# power_supply.net
KiCad netlist of a schematic drawn in Altium Designer
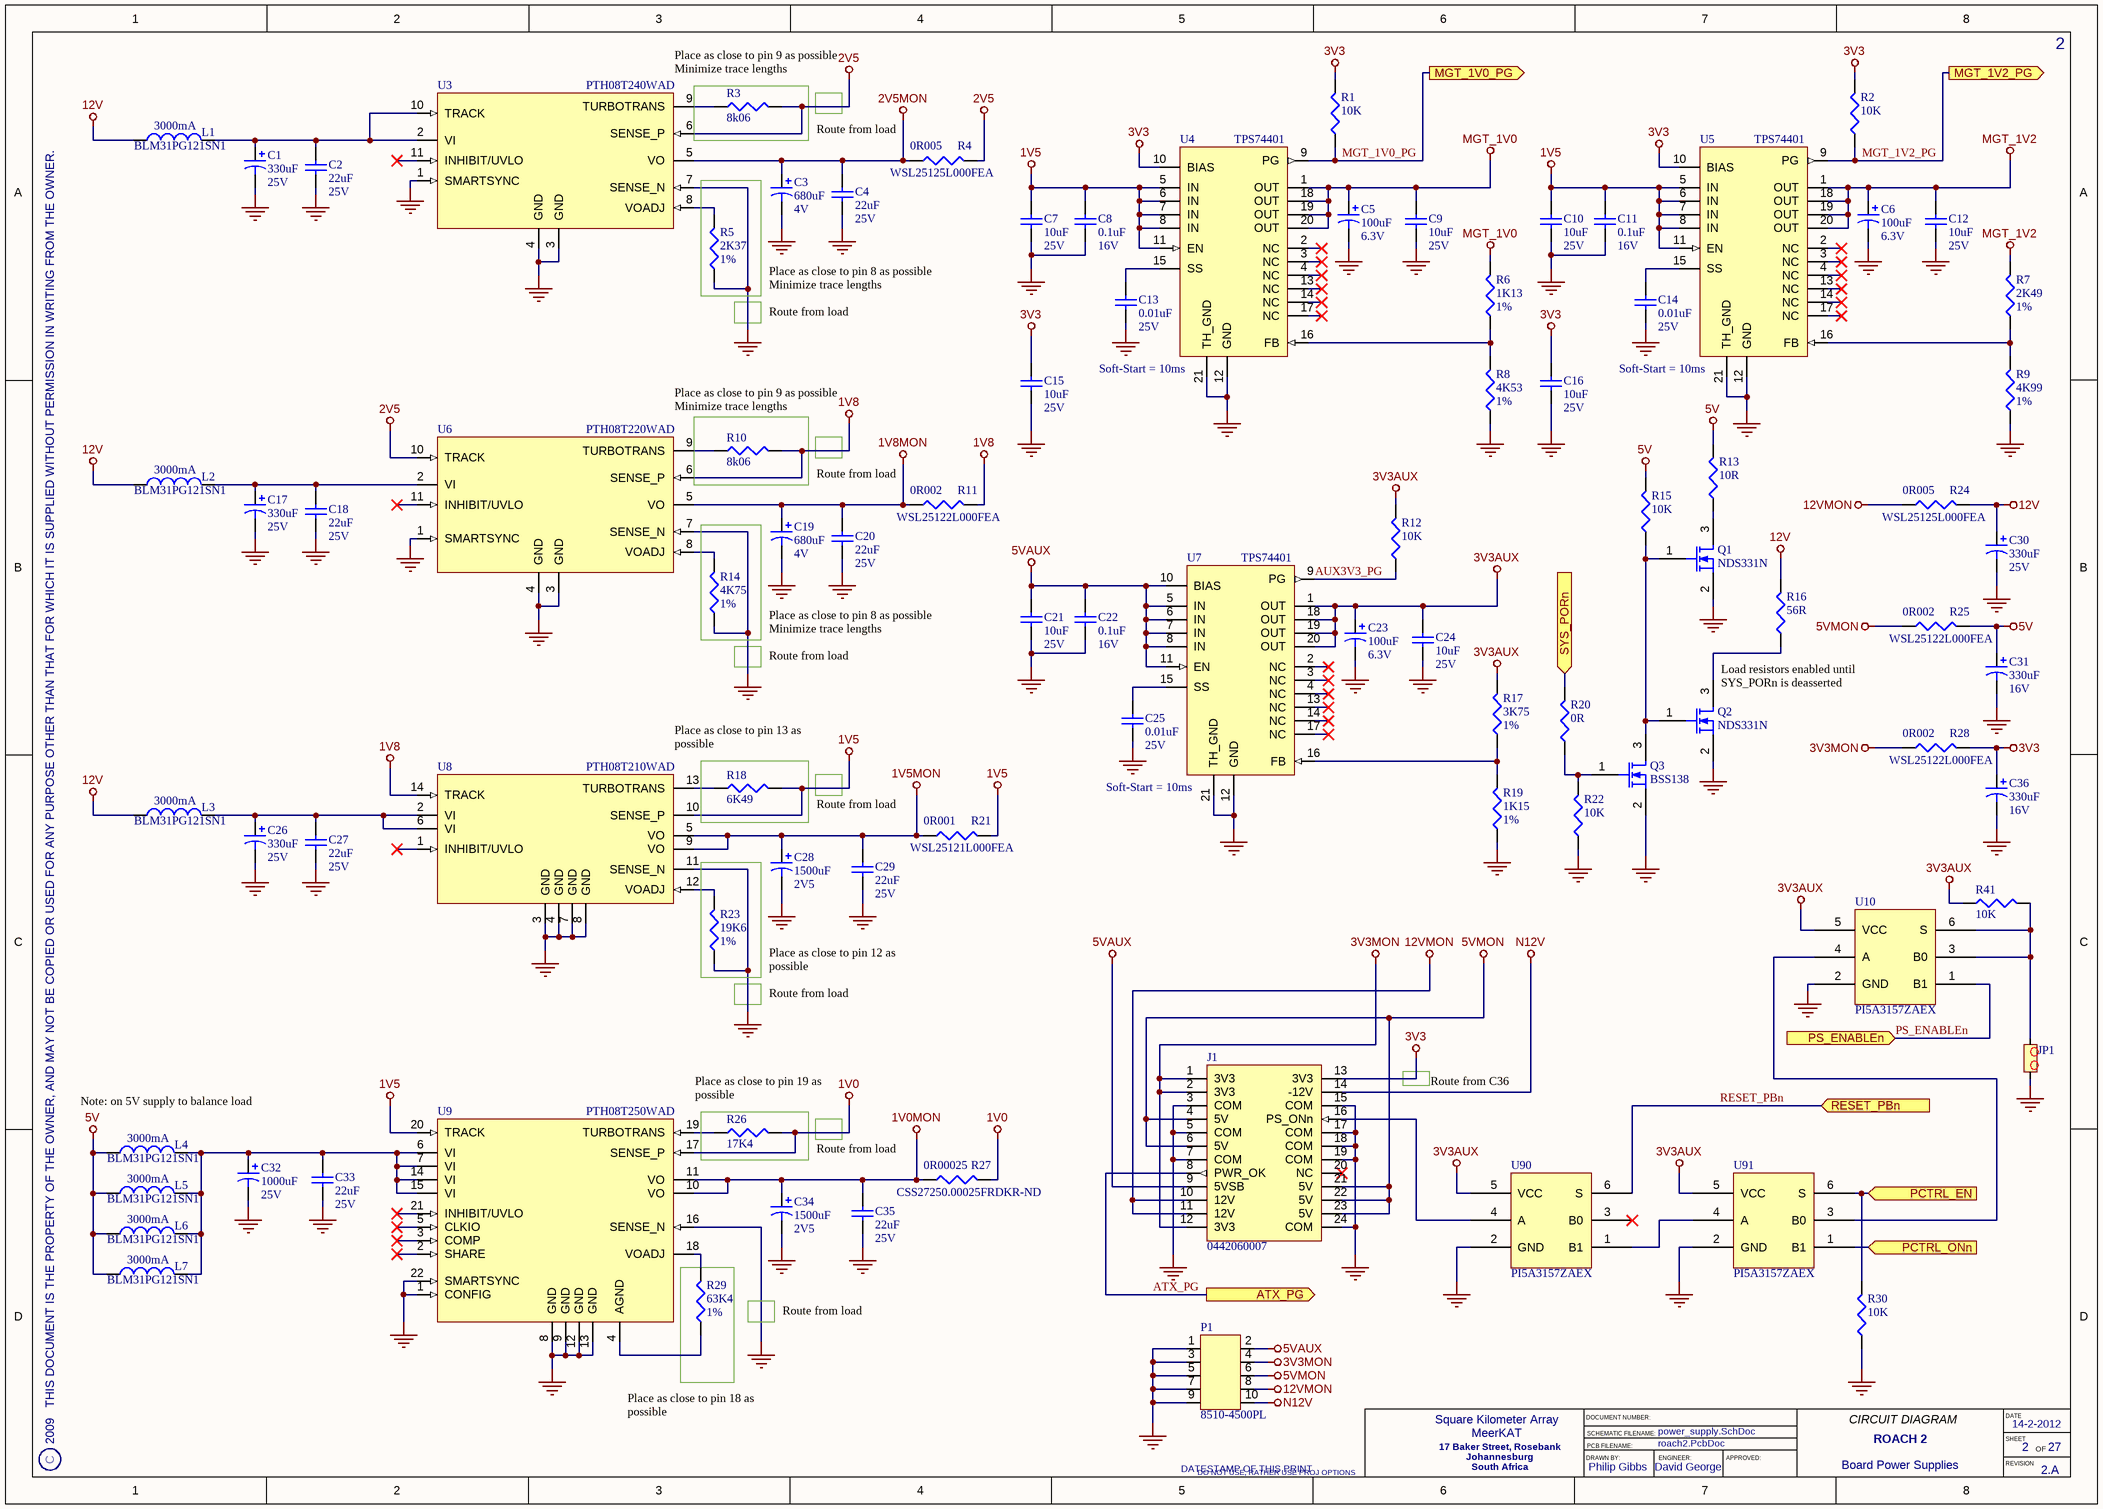
[diagram p0: power_supply.SchDoc]

(export (version "E")
  (design (tool "Eeschema 10.0.6"))
  (components
    (comp (ref "C1")
      (value "330uF")
      (footprint "EEE1CA331UP")
      (description "330uF, Surface Mount, Radial, Aluminium Electrolytic Capacitor")
      (fields
        (field (name "RATING") "25V")
        (field (name "MANUFACTURER") "PANASONIC-ECG")
        (field (name "PARTNUM") "EEE1EA331UP")
      )
      (libsource (lib "altium_db") (part "CapPol"))
    )
    (comp (ref "C2")
      (value "22uF")
      (footprint "CAPC3225X270L")
      (description "22uF, Ceramic Capacitor")
      (fields
        (field (name "RATING") "25V")
        (field (name "MANUFACTURER") "MURATA")
        (field (name "PARTNUM") "GRM32ER61E226ME15L")
      )
      (libsource (lib "altium_db") (part "CapStd"))
    )
    (comp (ref "C3")
      (value "680uF")
      (footprint "CAPMP7343X430L")
      (description "680uF, Conductive Polymer Chip Capacitor")
      (fields
        (field (name "RATING") "4V")
        (field (name "MANUFACTURER") "KEMET")
        (field (name "PARTNUM") "T520Y687M004ATE015")
      )
      (libsource (lib "altium_db") (part "CapPol"))
    )
    (comp (ref "C4")
      (value "22uF")
      (footprint "CAPC3225X270L")
      (description "22uF, Ceramic Capacitor")
      (fields
        (field (name "RATING") "25V")
        (field (name "MANUFACTURER") "MURATA")
        (field (name "PARTNUM") "GRM32ER61E226ME15L")
      )
      (libsource (lib "altium_db") (part "CapStd"))
    )
    (comp (ref "C5")
      (value "100uF")
      (footprint "CAPMP3528X210L")
      (description "100uF, Low ESR, Tantalum Capacitor")
      (fields
        (field (name "RATING") "6.3V")
        (field (name "MANUFACTURER") "AVX")
        (field (name "PARTNUM") "TPSB107M006R0200")
      )
      (libsource (lib "altium_db") (part "CapPol"))
    )
    (comp (ref "C6")
      (value "100uF")
      (footprint "CAPMP3528X210L")
      (description "100uF, Low ESR, Tantalum Capacitor")
      (fields
        (field (name "RATING") "6.3V")
        (field (name "MANUFACTURER") "AVX")
        (field (name "PARTNUM") "TPSB107M006R0200")
      )
      (libsource (lib "altium_db") (part "CapPol"))
    )
    (comp (ref "C7")
      (value "10uF")
      (footprint "CAPC3225X200L")
      (description "10uF, Ceramic Capacitor")
      (fields
        (field (name "RATING") "25V")
        (field (name "MANUFACTURER") "MURATA")
        (field (name "PARTNUM") "GRM32DR61E106KA12L")
      )
      (libsource (lib "altium_db") (part "CapStd"))
    )
    (comp (ref "C8")
      (value "0.1uF")
      (footprint "CAPC1005X60L")
      (description "0.1uF, Ceramic Capacitor")
      (fields
        (field (name "RATING") "16V")
        (field (name "MANUFACTURER") "VENKEL")
        (field (name "PARTNUM") "C0402X7R160-104KN")
      )
      (libsource (lib "altium_db") (part "CapStd"))
    )
    (comp (ref "C9")
      (value "10uF")
      (footprint "CAPC3225X200L")
      (description "10uF, Ceramic Capacitor")
      (fields
        (field (name "RATING") "25V")
        (field (name "MANUFACTURER") "MURATA")
        (field (name "PARTNUM") "GRM32DR61E106KA12L")
      )
      (libsource (lib "altium_db") (part "CapStd"))
    )
    (comp (ref "C10")
      (value "10uF")
      (footprint "CAPC3225X200L")
      (description "10uF, Ceramic Capacitor")
      (fields
        (field (name "RATING") "25V")
        (field (name "MANUFACTURER") "MURATA")
        (field (name "PARTNUM") "GRM32DR61E106KA12L")
      )
      (libsource (lib "altium_db") (part "CapStd"))
    )
    (comp (ref "C11")
      (value "0.1uF")
      (footprint "CAPC1005X60L")
      (description "0.1uF, Ceramic Capacitor")
      (fields
        (field (name "RATING") "16V")
        (field (name "MANUFACTURER") "VENKEL")
        (field (name "PARTNUM") "C0402X7R160-104KN")
      )
      (libsource (lib "altium_db") (part "CapStd"))
    )
    (comp (ref "C12")
      (value "10uF")
      (footprint "CAPC3225X200L")
      (description "10uF, Ceramic Capacitor")
      (fields
        (field (name "RATING") "25V")
        (field (name "MANUFACTURER") "MURATA")
        (field (name "PARTNUM") "GRM32DR61E106KA12L")
      )
      (libsource (lib "altium_db") (part "CapStd"))
    )
    (comp (ref "C13")
      (value "0.01uF")
      (footprint "CAPC1005X55L")
      (description "0.01uF, Ceramic Capacitor")
      (fields
        (field (name "RATING") "25V")
        (field (name "MANUFACTURER") "MURATA")
        (field (name "PARTNUM") "GRM155R71E103KA01D")
      )
      (libsource (lib "altium_db") (part "CapStd"))
    )
    (comp (ref "C14")
      (value "0.01uF")
      (footprint "CAPC1005X55L")
      (description "0.01uF, Ceramic Capacitor")
      (fields
        (field (name "RATING") "25V")
        (field (name "MANUFACTURER") "MURATA")
        (field (name "PARTNUM") "GRM155R71E103KA01D")
      )
      (libsource (lib "altium_db") (part "CapStd"))
    )
    (comp (ref "C15")
      (value "10uF")
      (footprint "CAPC3225X200L")
      (description "10uF, Ceramic Capacitor")
      (fields
        (field (name "RATING") "25V")
        (field (name "MANUFACTURER") "MURATA")
        (field (name "PARTNUM") "GRM32DR61E106KA12L")
      )
      (libsource (lib "altium_db") (part "CapStd"))
    )
    (comp (ref "C16")
      (value "10uF")
      (footprint "CAPC3225X200L")
      (description "10uF, Ceramic Capacitor")
      (fields
        (field (name "RATING") "25V")
        (field (name "MANUFACTURER") "MURATA")
        (field (name "PARTNUM") "GRM32DR61E106KA12L")
      )
      (libsource (lib "altium_db") (part "CapStd"))
    )
    (comp (ref "C17")
      (value "330uF")
      (footprint "EEE1CA331UP")
      (description "330uF, Surface Mount, Radial, Aluminium Electrolytic Capacitor")
      (fields
        (field (name "RATING") "25V")
        (field (name "MANUFACTURER") "PANASONIC-ECG")
        (field (name "PARTNUM") "EEE1EA331UP")
      )
      (libsource (lib "altium_db") (part "CapPol"))
    )
    (comp (ref "C18")
      (value "22uF")
      (footprint "CAPC3225X270L")
      (description "22uF, Ceramic Capacitor")
      (fields
        (field (name "RATING") "25V")
        (field (name "MANUFACTURER") "MURATA")
        (field (name "PARTNUM") "GRM32ER61E226ME15L")
      )
      (libsource (lib "altium_db") (part "CapStd"))
    )
    (comp (ref "C19")
      (value "680uF")
      (footprint "CAPMP7343X430L")
      (description "680uF, Conductive Polymer Chip Capacitor")
      (fields
        (field (name "RATING") "4V")
        (field (name "MANUFACTURER") "KEMET")
        (field (name "PARTNUM") "T520Y687M004ATE015")
      )
      (libsource (lib "altium_db") (part "CapPol"))
    )
    (comp (ref "C20")
      (value "22uF")
      (footprint "CAPC3225X270L")
      (description "22uF, Ceramic Capacitor")
      (fields
        (field (name "RATING") "25V")
        (field (name "MANUFACTURER") "MURATA")
        (field (name "PARTNUM") "GRM32ER61E226ME15L")
      )
      (libsource (lib "altium_db") (part "CapStd"))
    )
    (comp (ref "C21")
      (value "10uF")
      (footprint "CAPC3225X200L")
      (description "10uF, Ceramic Capacitor")
      (fields
        (field (name "RATING") "25V")
        (field (name "MANUFACTURER") "MURATA")
        (field (name "PARTNUM") "GRM32DR61E106KA12L")
      )
      (libsource (lib "altium_db") (part "CapStd"))
    )
    (comp (ref "C22")
      (value "0.1uF")
      (footprint "CAPC1005X60L")
      (description "0.1uF, Ceramic Capacitor")
      (fields
        (field (name "RATING") "16V")
        (field (name "MANUFACTURER") "VENKEL")
        (field (name "PARTNUM") "C0402X7R160-104KN")
      )
      (libsource (lib "altium_db") (part "CapStd"))
    )
    (comp (ref "C23")
      (value "100uF")
      (footprint "CAPMP3528X210L")
      (description "100uF, Low ESR, Tantalum Capacitor")
      (fields
        (field (name "RATING") "6.3V")
        (field (name "MANUFACTURER") "AVX")
        (field (name "PARTNUM") "TPSB107M006R0200")
      )
      (libsource (lib "altium_db") (part "CapPol"))
    )
    (comp (ref "C24")
      (value "10uF")
      (footprint "CAPC3225X200L")
      (description "10uF, Ceramic Capacitor")
      (fields
        (field (name "RATING") "25V")
        (field (name "MANUFACTURER") "MURATA")
        (field (name "PARTNUM") "GRM32DR61E106KA12L")
      )
      (libsource (lib "altium_db") (part "CapStd"))
    )
    (comp (ref "C25")
      (value "0.01uF")
      (footprint "CAPC1005X55L")
      (description "0.01uF, Ceramic Capacitor")
      (fields
        (field (name "RATING") "25V")
        (field (name "MANUFACTURER") "MURATA")
        (field (name "PARTNUM") "GRM155R71E103KA01D")
      )
      (libsource (lib "altium_db") (part "CapStd"))
    )
    (comp (ref "C26")
      (value "330uF")
      (footprint "EEE1CA331UP")
      (description "330uF, Surface Mount, Radial, Aluminium Electrolytic Capacitor")
      (fields
        (field (name "RATING") "25V")
        (field (name "MANUFACTURER") "PANASONIC-ECG")
        (field (name "PARTNUM") "EEE1EA331UP")
      )
      (libsource (lib "altium_db") (part "CapPol"))
    )
    (comp (ref "C27")
      (value "22uF")
      (footprint "CAPC3225X270L")
      (description "22uF, Ceramic Capacitor")
      (fields
        (field (name "RATING") "25V")
        (field (name "MANUFACTURER") "MURATA")
        (field (name "PARTNUM") "GRM32ER61E226ME15L")
      )
      (libsource (lib "altium_db") (part "CapStd"))
    )
    (comp (ref "C28")
      (value "1500uF")
      (footprint "CAPMP7343X430L")
      (description "1500uF, Conductive Polymer Chip Capacitor")
      (fields
        (field (name "RATING") "2V5")
        (field (name "MANUFACTURER") "KEMET")
        (field (name "PARTNUM") "T530X158M2R5ATE005")
      )
      (libsource (lib "altium_db") (part "CapPol"))
    )
    (comp (ref "C29")
      (value "22uF")
      (footprint "CAPC3225X270L")
      (description "22uF, Ceramic Capacitor")
      (fields
        (field (name "RATING") "25V")
        (field (name "MANUFACTURER") "MURATA")
        (field (name "PARTNUM") "GRM32ER61E226ME15L")
      )
      (libsource (lib "altium_db") (part "CapStd"))
    )
    (comp (ref "C30")
      (value "330uF")
      (footprint "EEE1CA331UP")
      (description "330uF, Surface Mount, Radial, Aluminium Electrolytic Capacitor")
      (fields
        (field (name "RATING") "25V")
        (field (name "MANUFACTURER") "PANASONIC-ECG")
        (field (name "PARTNUM") "EEE1EA331UP")
      )
      (libsource (lib "altium_db") (part "CapPol"))
    )
    (comp (ref "C31")
      (value "330uF")
      (footprint "CAPMP7263X380L")
      (description "330uF, Solid Tantalum Chip Capacitor")
      (fields
        (field (name "RATING") "16V")
        (field (name "MANUFACTURER") "VISHAY")
        (field (name "PARTNUM") "594D337X0016R2T")
      )
      (libsource (lib "altium_db") (part "CapPol"))
    )
    (comp (ref "C32")
      (value "1000uF")
      (footprint "CAPPRD750W80D1600H1500P")
      (description "1000uF, Aluminium Electrolytic Capacitor")
      (fields
        (field (name "RATING") "25V")
        (field (name "MANUFACTURER") "PANASONIC-ECG")
        (field (name "PARTNUM") "EEUFC1E102S")
      )
      (libsource (lib "altium_db") (part "CapPol"))
    )
    (comp (ref "C33")
      (value "22uF")
      (footprint "CAPC3225X270L")
      (description "22uF, Ceramic Capacitor")
      (fields
        (field (name "RATING") "25V")
        (field (name "MANUFACTURER") "MURATA")
        (field (name "PARTNUM") "GRM32ER61E226ME15L")
      )
      (libsource (lib "altium_db") (part "CapStd"))
    )
    (comp (ref "C34")
      (value "1500uF")
      (footprint "CAPMP7343X430L")
      (description "1500uF, Conductive Polymer Chip Capacitor")
      (fields
        (field (name "RATING") "2V5")
        (field (name "MANUFACTURER") "KEMET")
        (field (name "PARTNUM") "T530X158M2R5ATE005")
      )
      (libsource (lib "altium_db") (part "CapPol"))
    )
    (comp (ref "C35")
      (value "22uF")
      (footprint "CAPC3225X270L")
      (description "22uF, Ceramic Capacitor")
      (fields
        (field (name "RATING") "25V")
        (field (name "MANUFACTURER") "MURATA")
        (field (name "PARTNUM") "GRM32ER61E226ME15L")
      )
      (libsource (lib "altium_db") (part "CapStd"))
    )
    (comp (ref "C36")
      (value "330uF")
      (footprint "CAPMP7263X380L")
      (description "330uF, Solid Tantalum Chip Capacitor")
      (fields
        (field (name "RATING") "16V")
        (field (name "MANUFACTURER") "VISHAY")
        (field (name "PARTNUM") "594D337X0016R2T")
      )
      (libsource (lib "altium_db") (part "CapPol"))
    )
    (comp (ref "J1")
      (value "0442060007")
      (footprint "MOLEX_0442060007")
      (description "24-Pin ATX Connector")
      (fields (field (name "PARTNUM") "0442060007") (field (name "MANUFACTURER") "Molex"))
      (libsource (lib "altium_db") (part "0442060007"))
    )
    (comp (ref "JP1")
      (value "0022032021")
      (footprint "MOLEX_0022032021")
      (description "1x2, 2.56mm, Header/Jumper")
      (fields (field (name "MANUFACTURER") "Molex"))
      (libsource (lib "altium_db") (part "con_hdr_1x2"))
    )
    (comp (ref "L1")
      (value "120R")
      (footprint "INDC3216X130L")
      (description "120 Ohm, Chip Ferrite Brad")
      (fields
        (field (name "RATING") "3000mA")
        (field (name "MANUFACTURER") "Murata")
        (field (name "PARTNUM") "BLM31PG121SN1")
        (field (name "TOLERANCE") "25%")
      )
      (libsource (lib "altium_db") (part "IndStd"))
    )
    (comp (ref "L2")
      (value "120R")
      (footprint "INDC3216X130L")
      (description "120 Ohm, Chip Ferrite Brad")
      (fields
        (field (name "RATING") "3000mA")
        (field (name "MANUFACTURER") "Murata")
        (field (name "PARTNUM") "BLM31PG121SN1")
        (field (name "TOLERANCE") "25%")
      )
      (libsource (lib "altium_db") (part "IndStd"))
    )
    (comp (ref "L3")
      (value "120R")
      (footprint "INDC3216X130L")
      (description "120 Ohm, Chip Ferrite Brad")
      (fields
        (field (name "RATING") "3000mA")
        (field (name "MANUFACTURER") "Murata")
        (field (name "PARTNUM") "BLM31PG121SN1")
        (field (name "TOLERANCE") "25%")
      )
      (libsource (lib "altium_db") (part "IndStd"))
    )
    (comp (ref "L4")
      (value "120R")
      (footprint "INDC3216X130L")
      (description "120 Ohm, Chip Ferrite Brad")
      (fields
        (field (name "RATING") "3000mA")
        (field (name "MANUFACTURER") "Murata")
        (field (name "PARTNUM") "BLM31PG121SN1")
        (field (name "TOLERANCE") "25%")
      )
      (libsource (lib "altium_db") (part "IndStd"))
    )
    (comp (ref "L5")
      (value "120R")
      (footprint "INDC3216X130L")
      (description "120 Ohm, Chip Ferrite Brad")
      (fields
        (field (name "RATING") "3000mA")
        (field (name "MANUFACTURER") "Murata")
        (field (name "PARTNUM") "BLM31PG121SN1")
        (field (name "TOLERANCE") "25%")
      )
      (libsource (lib "altium_db") (part "IndStd"))
    )
    (comp (ref "L6")
      (value "120R")
      (footprint "INDC3216X130L")
      (description "120 Ohm, Chip Ferrite Brad")
      (fields
        (field (name "RATING") "3000mA")
        (field (name "MANUFACTURER") "Murata")
        (field (name "PARTNUM") "BLM31PG121SN1")
        (field (name "TOLERANCE") "25%")
      )
      (libsource (lib "altium_db") (part "IndStd"))
    )
    (comp (ref "L7")
      (value "120R")
      (footprint "INDC3216X130L")
      (description "120 Ohm, Chip Ferrite Brad")
      (fields
        (field (name "RATING") "3000mA")
        (field (name "MANUFACTURER") "Murata")
        (field (name "PARTNUM") "BLM31PG121SN1")
        (field (name "TOLERANCE") "25%")
      )
      (libsource (lib "altium_db") (part "IndStd"))
    )
    (comp (ref "P1")
      (value "8510-4500PL")
      (footprint "3M_8510-4500PL")
      (description "2x5, 2.54 mm Pitch, Through-hole, 1 Amp, Female Header")
      (fields (field (name "PARTNUM") "8510-4500PL") (field (name "MANUFACTURER") "3M"))
      (libsource (lib "altium_db") (part "con_hdr_2x5"))
    )
    (comp (ref "Q1")
      (value "NDS331N")
      (footprint "SOT95P245X110-3N")
      (description "N-Channel Logic Level Enhancement Mode Field Effect Transistor")
      (fields (field (name "MANUFACTURER") "Fairchild Semiconductor"))
      (libsource (lib "altium_db") (part "NDS331N"))
    )
    (comp (ref "Q2")
      (value "NDS331N")
      (footprint "SOT95P245X110-3N")
      (description "N-Channel Logic Level Enhancement Mode Field Effect Transistor")
      (fields (field (name "MANUFACTURER") "Fairchild Semiconductor"))
      (libsource (lib "altium_db") (part "NDS331N"))
    )
    (comp (ref "Q3")
      (value "BSS138")
      (footprint "SOT95P245X110-3N")
      (description "N-Channel Logic Level Enhancement Mode Field Effect Transistor")
      (fields (field (name "MANUFACTURER") "Fairchild Semiconductor"))
      (libsource (lib "altium_db") (part "BSS138"))
    )
    (comp (ref "R1")
      (value "10K")
      (footprint "RESC1005X40L")
      (description "10K, 1.1mm x 0.5mm, Thick Film Resistor")
      (fields (field (name "MANUFACTURER") "ROYALOHM") (field (name "PARTNUM") "0402WGJ0103T1E"))
      (libsource (lib "altium_db") (part "ResStd"))
    )
    (comp (ref "R2")
      (value "10K")
      (footprint "RESC1005X40L")
      (description "10K, 1.1mm x 0.5mm, Thick Film Resistor")
      (fields (field (name "MANUFACTURER") "ROYALOHM") (field (name "PARTNUM") "0402WGJ0103T1E"))
      (libsource (lib "altium_db") (part "ResStd"))
    )
    (comp (ref "R3")
      (value "8k06")
      (footprint "RESC1005X40L")
      (description "8K06, 1.1mm x 0.5mm, Thick Film Resistor")
      (fields (field (name "Comment") "ResStd"))
      (libsource (lib "altium_db") (part "ResStd"))
    )
    (comp (ref "R4")
      (value "0R005")
      (footprint "RESC6332X90M")
      (description "5 milliohm, Power Metal Strip, Sense Resistor")
      (fields
        (field (name "MANUFACTURER") "VISHAY")
        (field (name "PARTNUM") "WSL25125L000FEA")
        (field (name "TOLERANCE") "1%")
      )
      (libsource (lib "altium_db") (part "ResStd"))
    )
    (comp (ref "R5")
      (value "2K37")
      (footprint "RESC1005X40L")
      (description "2K37, 1.1mm x 0.5mm, Thick Film Resistor")
      (fields
        (field (name "MANUFACTURER") "ROYALOHM")
        (field (name "PARTNUM") "0402WGF2371T1E")
        (field (name "TOLERANCE") "1%")
      )
      (libsource (lib "altium_db") (part "ResStd"))
    )
    (comp (ref "R6")
      (value "1K13")
      (footprint "RESC1005X40L")
      (description "1K13, 1.1mm x 0.5mm, Thick Film Resistor")
      (fields
        (field (name "MANUFACTURER") "ROYALOHM")
        (field (name "PARTNUM") "0402WGF1131T1E")
        (field (name "TOLERANCE") "1%")
      )
      (libsource (lib "altium_db") (part "ResStd"))
    )
    (comp (ref "R7")
      (value "2K49")
      (footprint "RESC1005X40L")
      (description "2K49, 1.1mm x 0.5mm, Thick Film Resistor")
      (fields
        (field (name "MANUFACTURER") "ROYALOHM")
        (field (name "PARTNUM") "0402WGF2K49T1E")
        (field (name "TOLERANCE") "1%")
      )
      (libsource (lib "altium_db") (part "ResStd"))
    )
    (comp (ref "R8")
      (value "4K53")
      (footprint "RESC1005X40L")
      (description "4K53, 1.1mm x 0.5mm, Thick Film Resistor")
      (fields
        (field (name "MANUFACTURER") "ROYALOHM")
        (field (name "PARTNUM") "0402WGF4531T1E")
        (field (name "TOLERANCE") "1%")
      )
      (libsource (lib "altium_db") (part "ResStd"))
    )
    (comp (ref "R9")
      (value "4K99")
      (footprint "RESC1005X40L")
      (description "4K99, 1.1mm x 0.5mm, Thick Film Resistor")
      (fields
        (field (name "MANUFACTURER") "ROYALOHM")
        (field (name "PARTNUM") "0402WGF4991T1E")
        (field (name "TOLERANCE") "1%")
      )
      (libsource (lib "altium_db") (part "ResStd"))
    )
    (comp (ref "R10")
      (value "8k06")
      (footprint "RESC1005X40L")
      (description "8K06, 1.1mm x 0.5mm, Thick Film Resistor")
      (fields (field (name "Comment") "ResStd"))
      (libsource (lib "altium_db") (part "ResStd"))
    )
    (comp (ref "R11")
      (value "0R002")
      (footprint "RESC6332X90M")
      (description "2 milliohm, Power Metal Strip, Sense Resistor")
      (fields
        (field (name "MANUFACTURER") "VISHAY")
        (field (name "PARTNUM") "WSL25122L000FEA")
        (field (name "TOLERANCE") "1%")
      )
      (libsource (lib "altium_db") (part "ResStd"))
    )
    (comp (ref "R12")
      (value "10K")
      (footprint "RESC1005X40L")
      (description "10K, 1.1mm x 0.5mm, Thick Film Resistor")
      (fields (field (name "MANUFACTURER") "ROYALOHM") (field (name "PARTNUM") "0402WGJ0103T1E"))
      (libsource (lib "altium_db") (part "ResStd"))
    )
    (comp (ref "R13")
      (value "10R")
      (footprint "VISHAY_AC5")
      (description "10R, Cemented Wire Round Resistor")
      (fields (field (name "MANUFACTURER") "VISHAY") (field (name "PARTNUM") "AC05000001009JLB00"))
      (libsource (lib "altium_db") (part "ResStd"))
    )
    (comp (ref "R14")
      (value "4K75")
      (footprint "RESC1005X40L")
      (description "4K75, 1.1mm x 0.5mm, Thick Film Resistor")
      (fields
        (field (name "MANUFACTURER") "ROYALOHM")
        (field (name "PARTNUM") "0402WGF4751T1E")
        (field (name "TOLERANCE") "1%")
      )
      (libsource (lib "altium_db") (part "ResStd"))
    )
    (comp (ref "R15")
      (value "10K")
      (footprint "RESC1005X40L")
      (description "10K, 1.1mm x 0.5mm, Thick Film Resistor")
      (fields (field (name "MANUFACTURER") "ROYALOHM") (field (name "PARTNUM") "0402WGJ0103T1E"))
      (libsource (lib "altium_db") (part "ResStd"))
    )
    (comp (ref "R16")
      (value "56R")
      (footprint "VISHAY_AC5")
      (description "56R, Cemented Wire Round Resistor")
      (fields (field (name "MANUFACTURER") "VISHAY") (field (name "PARTNUM") "AC05000001009JLB00"))
      (libsource (lib "altium_db") (part "ResStd"))
    )
    (comp (ref "R17")
      (value "3K75")
      (footprint "RESC1005X40L")
      (description "3K57, 1.1mm x 0.5mm, Thick Film Resistor")
      (fields
        (field (name "MANUFACTURER") "ROYALOHM")
        (field (name "PARTNUM") "0402WGF3751T1E")
        (field (name "TOLERANCE") "1%")
      )
      (libsource (lib "altium_db") (part "ResStd"))
    )
    (comp (ref "R18")
      (value "6K49")
      (footprint "RESC1005X40L")
      (description "6K49, 1.1mm x 0.5mm, Thick Film Resistor")
      (fields (field (name "Comment") "ResStd"))
      (libsource (lib "altium_db") (part "ResStd"))
    )
    (comp (ref "R19")
      (value "1K15")
      (footprint "RESC1005X40L")
      (description "1K15, 1.1mm x 0.5mm, Thick Film Resistor")
      (fields
        (field (name "MANUFACTURER") "ROYALOHM")
        (field (name "PARTNUM") "0402WGF1150T1E")
        (field (name "TOLERANCE") "1%")
      )
      (libsource (lib "altium_db") (part "ResStd"))
    )
    (comp (ref "R20")
      (value "0R")
      (footprint "RESC1005X40L")
      (description "0R, 1.1mm x 0.5mm, Thick Film Resistor")
      (fields (field (name "MANUFACTURER") "ROYALOHM") (field (name "PARTNUM") "0402WG00000T1E"))
      (libsource (lib "altium_db") (part "ResStd"))
    )
    (comp (ref "R21")
      (value "0R001")
      (footprint "RESC6332X90M")
      (description "1 milliohm, Power Metal Strip, Sense Resistor")
      (fields
        (field (name "MANUFACTURER") "VISHAY")
        (field (name "PARTNUM") "WSL25121L000FEA")
        (field (name "TOLERANCE") "1%")
      )
      (libsource (lib "altium_db") (part "ResStd"))
    )
    (comp (ref "R22")
      (value "10K")
      (footprint "RESC1005X40L")
      (description "10K, 1.1mm x 0.5mm, Thick Film Resistor")
      (fields (field (name "MANUFACTURER") "ROYALOHM") (field (name "PARTNUM") "0402WGJ0103T1E"))
      (libsource (lib "altium_db") (part "ResStd"))
    )
    (comp (ref "R23")
      (value "19K6")
      (footprint "RESC1005X40L")
      (description "19K6, 1.1mm x 0.5mm, Thick Film Resistor")
      (fields
        (field (name "MANUFACTURER") "ROYALOHM")
        (field (name "PARTNUM") "0402WGF1962T1E")
        (field (name "TOLERANCE") "1%")
      )
      (libsource (lib "altium_db") (part "ResStd"))
    )
    (comp (ref "R24")
      (value "0R005")
      (footprint "RESC6332X90M")
      (description "5 milliohm, Power Metal Strip, Sense Resistor")
      (fields
        (field (name "MANUFACTURER") "VISHAY")
        (field (name "PARTNUM") "WSL25125L000FEA")
        (field (name "TOLERANCE") "1%")
      )
      (libsource (lib "altium_db") (part "ResStd"))
    )
    (comp (ref "R25")
      (value "0R002")
      (footprint "RESC6332X90M")
      (description "2 milliohm, Power Metal Strip, Sense Resistor")
      (fields
        (field (name "MANUFACTURER") "VISHAY")
        (field (name "PARTNUM") "WSL25122L000FEA")
        (field (name "TOLERANCE") "1%")
      )
      (libsource (lib "altium_db") (part "ResStd"))
    )
    (comp (ref "R26")
      (value "17K4")
      (footprint "RESC1005X40L")
      (description "17K4, 1.1mm x 0.5mm, Thick Film Resistor")
      (fields (field (name "Comment") "ResStd"))
      (libsource (lib "altium_db") (part "ResStd"))
    )
    (comp (ref "R27")
      (value "0R00025")
      (footprint "RESC6867X140M")
      (description "0.25 milliohm, Power Metal Foil;, Sense Resistor")
      (fields
        (field (name "MANUFACTURER") "STACKPOLE")
        (field (name "PARTNUM") "CSS27250.00025FRDKR-ND")
        (field (name "TOLERANCE") "1%")
      )
      (libsource (lib "altium_db") (part "ResStd"))
    )
    (comp (ref "R28")
      (value "0R002")
      (footprint "RESC6332X90M")
      (description "2 milliohm, Power Metal Strip, Sense Resistor")
      (fields
        (field (name "MANUFACTURER") "VISHAY")
        (field (name "PARTNUM") "WSL25122L000FEA")
        (field (name "TOLERANCE") "1%")
      )
      (libsource (lib "altium_db") (part "ResStd"))
    )
    (comp (ref "R29")
      (value "63K4")
      (footprint "RESC1005X40L")
      (description "63K4, 1.1mm x 0.5mm, Thick Film Resistor")
      (fields
        (field (name "MANUFACTURER") "ROYALOHM")
        (field (name "PARTNUM") "0402WGF6342T1E")
        (field (name "TOLERANCE") "1%")
      )
      (libsource (lib "altium_db") (part "ResStd"))
    )
    (comp (ref "R30")
      (value "10K")
      (footprint "RESC1005X40L")
      (description "10K, 1.1mm x 0.5mm, Thick Film Resistor")
      (fields (field (name "MANUFACTURER") "ROYALOHM") (field (name "PARTNUM") "0402WGJ0103T1E"))
      (libsource (lib "altium_db") (part "ResStd"))
    )
    (comp (ref "R41")
      (value "10K")
      (footprint "RESC1005X40L")
      (description "10K, 1.1mm x 0.5mm, Thick Film Resistor")
      (fields (field (name "MANUFACTURER") "ROYALOHM") (field (name "PARTNUM") "0402WGJ0103T1E"))
      (libsource (lib "altium_db") (part "ResStd"))
    )
    (comp (ref "U3")
      (value "PTH08T240WAD")
      (footprint "DIP_Module_11PIN-A")
      (description "10-A, 4.5-V to 14-V INPUT, NON-ISOLATED, WIDE-OUTPUT, ADJUSTABLE POWER MODULE WITH TurboTrans")
      (fields (field (name "MANUFACTURER") "Texas Instruments"))
      (libsource (lib "altium_db") (part "PTH08T240W"))
    )
    (comp (ref "U4")
      (value "TPS74401")
      (footprint "VQFN20")
      (description "3.0A Ultra-LDO with Programmable Soft-Start")
      (fields (field (name "MANUFACTURER") "Texas Instruments"))
      (libsource (lib "altium_db") (part "TPS74401"))
    )
    (comp (ref "U5")
      (value "TPS74401")
      (footprint "VQFN20")
      (description "3.0A Ultra-LDO with Programmable Soft-Start")
      (fields (field (name "MANUFACTURER") "Texas Instruments"))
      (libsource (lib "altium_db") (part "TPS74401"))
    )
    (comp (ref "U6")
      (value "PTH08T220WAD")
      (footprint "DIP_Module_11PIN")
      (description "16-A, 4.5-V to 14-V INPUT, NON-ISOLATED, WIDE-OUTPUT, ADJUSTABLE POWER MODULE WITH TurboTrans")
      (fields (field (name "MANUFACTURER") "Texas Instruments"))
      (libsource (lib "altium_db") (part "PTH08T220W"))
    )
    (comp (ref "U7")
      (value "TPS74401")
      (footprint "VQFN20")
      (description "3.0A Ultra-LDO with Programmable Soft-Start")
      (fields (field (name "MANUFACTURER") "Texas Instruments"))
      (libsource (lib "altium_db") (part "TPS74401"))
    )
    (comp (ref "U8")
      (value "PTH08T210WAD")
      (footprint "DIP_Module_14PIN")
      (description "30-A, 5.5V-14-V INPUT, NON-ISOLATED, WIDE OUTPUT ADJUST, POWER MODULE WITH TURBOTRANS")
      (fields (field (name "MANUFACTURER") "Texas Instruments"))
      (libsource (lib "altium_db") (part "PTH08T210W"))
    )
    (comp (ref "U9")
      (value "PTH08T250WAD")
      (footprint "DIP_Module_22PIN")
      (description "50-A, 4.5-V to 14-V INPUT, NON-ISOLATED,  WIDE-OUTPUT, ADJUSTABLE POWER MODULE WITH TurboTrans")
      (fields (field (name "MANUFACTURER") "Texas Instruments"))
      (libsource (lib "altium_db") (part "PTH08T250W"))
    )
    (comp (ref "U10")
      (value "PI5A3157ZAEX")
      (footprint "SC70-6")
      (description "Low voltage SPDT Analogue Switch")
      (fields (field (name "MANUFACTURER") "PERICOM"))
      (libsource (lib "altium_db") (part "PI5A3157ZAEX"))
    )
    (comp (ref "U90")
      (value "PI5A3157ZAEX")
      (footprint "SC70-6")
      (description "Low voltage SPDT Analogue Switch")
      (fields (field (name "MANUFACTURER") "PERICOM"))
      (libsource (lib "altium_db") (part "PI5A3157ZAEX"))
    )
    (comp (ref "U91")
      (value "PI5A3157ZAEX")
      (footprint "SC70-6")
      (description "Low voltage SPDT Analogue Switch")
      (fields (field (name "MANUFACTURER") "PERICOM"))
      (libsource (lib "altium_db") (part "PI5A3157ZAEX"))
    )
  )
  (nets
    (net (code "1") (name "/ATX_PG") (class "Default")
      (node (ref "J1") (pin "8") (pinfunction "PWR_OK_8") (pintype "output"))
    )
    (net (code "2") (name "/AUX3V3_PG") (class "Default")
      (node (ref "R12") (pin "1") (pinfunction "1_1") (pintype "passive"))
      (node (ref "U7") (pin "9") (pinfunction "PG_9") (pintype "output"))
    )
    (net (code "3") (name "/MGT_1V0_PG") (class "Default")
      (node (ref "R1") (pin "1") (pinfunction "1_1") (pintype "passive"))
      (node (ref "U4") (pin "9") (pinfunction "PG_9") (pintype "output"))
    )
    (net (code "4") (name "/MGT_1V2_PG") (class "Default")
      (node (ref "R2") (pin "1") (pinfunction "1_1") (pintype "passive"))
      (node (ref "U5") (pin "9") (pinfunction "PG_9") (pintype "output"))
    )
    (net (code "5") (name "/PCTRL_EN") (class "Default")
      (node (ref "R30") (pin "2") (pinfunction "2_2") (pintype "passive"))
      (node (ref "U91") (pin "6") (pinfunction "S_6") (pintype "passive"))
    )
    (net (code "6") (name "/PCTRL_ONn") (class "Default")
      (node (ref "U91") (pin "1") (pinfunction "B1_1") (pintype "passive"))
    )
    (net (code "7") (name "/PS_ENABLEn") (class "Default")
      (node (ref "U10") (pin "1") (pinfunction "B1_1") (pintype "passive"))
    )
    (net (code "8") (name "/RESET_PBn") (class "Default")
      (node (ref "U90") (pin "6") (pinfunction "S_6") (pintype "passive"))
    )
    (net (code "9") (name "/SYS_PORn") (class "Default")
      (node (ref "R20") (pin "2") (pinfunction "2_2") (pintype "passive"))
    )
    (net (code "10") (name "1V0") (class "Default")
      (node (ref "R26") (pin "2") (pinfunction "2_2") (pintype "passive"))
      (node (ref "R27") (pin "2") (pinfunction "2_2") (pintype "passive"))
      (node (ref "U9") (pin "17") (pinfunction "SENSE_P_17") (pintype "input"))
    )
    (net (code "11") (name "1V0MON") (class "Default")
      (node (ref "C34") (pin "1") (pinfunction "1_1") (pintype "passive"))
      (node (ref "C35") (pin "2") (pinfunction "2_2") (pintype "passive"))
      (node (ref "R27") (pin "1") (pinfunction "1_1") (pintype "passive"))
      (node (ref "U9") (pin "10") (pinfunction "VO_10") (pintype "power_in"))
      (node (ref "U9") (pin "11") (pinfunction "VO_11") (pintype "power_in"))
    )
    (net (code "12") (name "1V5") (class "Default")
      (node (ref "C10") (pin "2") (pinfunction "2_2") (pintype "passive"))
      (node (ref "C11") (pin "2") (pinfunction "2_2") (pintype "passive"))
      (node (ref "C7") (pin "2") (pinfunction "2_2") (pintype "passive"))
      (node (ref "C8") (pin "2") (pinfunction "2_2") (pintype "passive"))
      (node (ref "R18") (pin "2") (pinfunction "2_2") (pintype "passive"))
      (node (ref "R21") (pin "2") (pinfunction "2_2") (pintype "passive"))
      (node (ref "U4") (pin "11") (pinfunction "EN_11") (pintype "input"))
      (node (ref "U4") (pin "5") (pinfunction "IN_5") (pintype "power_in"))
      (node (ref "U4") (pin "6") (pinfunction "IN_6") (pintype "power_in"))
      (node (ref "U4") (pin "7") (pinfunction "IN_7") (pintype "power_in"))
      (node (ref "U4") (pin "8") (pinfunction "IN_8") (pintype "power_in"))
      (node (ref "U5") (pin "11") (pinfunction "EN_11") (pintype "input"))
      (node (ref "U5") (pin "5") (pinfunction "IN_5") (pintype "power_in"))
      (node (ref "U5") (pin "6") (pinfunction "IN_6") (pintype "power_in"))
      (node (ref "U5") (pin "7") (pinfunction "IN_7") (pintype "power_in"))
      (node (ref "U5") (pin "8") (pinfunction "IN_8") (pintype "power_in"))
      (node (ref "U8") (pin "10") (pinfunction "SENSE_P_10") (pintype "power_in"))
      (node (ref "U9") (pin "20") (pinfunction "TRACK_20") (pintype "input"))
    )
    (net (code "13") (name "1V5MON") (class "Default")
      (node (ref "C28") (pin "1") (pinfunction "1_1") (pintype "passive"))
      (node (ref "C29") (pin "2") (pinfunction "2_2") (pintype "passive"))
      (node (ref "R21") (pin "1") (pinfunction "1_1") (pintype "passive"))
      (node (ref "U8") (pin "5") (pinfunction "VO_5") (pintype "power_in"))
      (node (ref "U8") (pin "9") (pinfunction "VO_9") (pintype "power_in"))
    )
    (net (code "14") (name "1V8") (class "Default")
      (node (ref "R10") (pin "2") (pinfunction "2_2") (pintype "passive"))
      (node (ref "R11") (pin "2") (pinfunction "2_2") (pintype "passive"))
      (node (ref "U6") (pin "6") (pinfunction "SENSE_P_6") (pintype "input"))
      (node (ref "U8") (pin "14") (pinfunction "TRACK_14") (pintype "input"))
    )
    (net (code "15") (name "1V8MON") (class "Default")
      (node (ref "C19") (pin "1") (pinfunction "1_1") (pintype "passive"))
      (node (ref "C20") (pin "2") (pinfunction "2_2") (pintype "passive"))
      (node (ref "R11") (pin "1") (pinfunction "1_1") (pintype "passive"))
      (node (ref "U6") (pin "5") (pinfunction "VO_5") (pintype "power_in"))
    )
    (net (code "16") (name "2V5") (class "Default")
      (node (ref "R3") (pin "2") (pinfunction "2_2") (pintype "passive"))
      (node (ref "R4") (pin "2") (pinfunction "2_2") (pintype "passive"))
      (node (ref "U3") (pin "6") (pinfunction "SENSE_P_6") (pintype "input"))
      (node (ref "U6") (pin "10") (pinfunction "TRACK_10") (pintype "input"))
    )
    (net (code "17") (name "2V5MON") (class "Default")
      (node (ref "C3") (pin "1") (pinfunction "1_1") (pintype "passive"))
      (node (ref "C4") (pin "2") (pinfunction "2_2") (pintype "passive"))
      (node (ref "R4") (pin "1") (pinfunction "1_1") (pintype "passive"))
      (node (ref "U3") (pin "5") (pinfunction "VO_5") (pintype "power_in"))
    )
    (net (code "18") (name "3V3") (class "Default")
      (node (ref "C15") (pin "2") (pinfunction "2_2") (pintype "passive"))
      (node (ref "C16") (pin "2") (pinfunction "2_2") (pintype "passive"))
      (node (ref "C36") (pin "1") (pinfunction "1_1") (pintype "passive"))
      (node (ref "J1") (pin "13") (pinfunction "3V3_13") (pintype "power_in"))
      (node (ref "R1") (pin "2") (pinfunction "2_2") (pintype "passive"))
      (node (ref "R2") (pin "2") (pinfunction "2_2") (pintype "passive"))
      (node (ref "R28") (pin "2") (pinfunction "2_2") (pintype "passive"))
      (node (ref "U4") (pin "10") (pinfunction "BIAS_10") (pintype "power_in"))
      (node (ref "U5") (pin "10") (pinfunction "BIAS_10") (pintype "power_in"))
    )
    (net (code "19") (name "3V3AUX") (class "Default")
      (node (ref "C23") (pin "1") (pinfunction "1_1") (pintype "passive"))
      (node (ref "C24") (pin "2") (pinfunction "2_2") (pintype "passive"))
      (node (ref "R12") (pin "2") (pinfunction "2_2") (pintype "passive"))
      (node (ref "R17") (pin "2") (pinfunction "2_2") (pintype "passive"))
      (node (ref "R41") (pin "1") (pinfunction "1_1") (pintype "passive"))
      (node (ref "U10") (pin "5") (pinfunction "VCC_5") (pintype "passive"))
      (node (ref "U7") (pin "1") (pinfunction "OUT_1") (pintype "power_in"))
      (node (ref "U7") (pin "18") (pinfunction "OUT_18") (pintype "power_in"))
      (node (ref "U7") (pin "19") (pinfunction "OUT_19") (pintype "power_in"))
      (node (ref "U7") (pin "20") (pinfunction "OUT_20") (pintype "power_in"))
      (node (ref "U90") (pin "5") (pinfunction "VCC_5") (pintype "passive"))
      (node (ref "U91") (pin "5") (pinfunction "VCC_5") (pintype "passive"))
    )
    (net (code "20") (name "3V3MON") (class "Default")
      (node (ref "J1") (pin "1") (pinfunction "3V3_1") (pintype "power_in"))
      (node (ref "J1") (pin "12") (pinfunction "3V3_12") (pintype "power_in"))
      (node (ref "J1") (pin "2") (pinfunction "3V3_2") (pintype "power_in"))
      (node (ref "P1") (pin "4") (pinfunction "4_4") (pintype "passive"))
      (node (ref "R28") (pin "1") (pinfunction "1_1") (pintype "passive"))
    )
    (net (code "21") (name "5V") (class "Default")
      (node (ref "C31") (pin "1") (pinfunction "1_1") (pintype "passive"))
      (node (ref "L4") (pin "1") (pinfunction "1_1") (pintype "passive"))
      (node (ref "L5") (pin "1") (pinfunction "1_1") (pintype "passive"))
      (node (ref "L6") (pin "1") (pinfunction "1_1") (pintype "passive"))
      (node (ref "L7") (pin "1") (pinfunction "1_1") (pintype "passive"))
      (node (ref "R13") (pin "2") (pinfunction "2_2") (pintype "passive"))
      (node (ref "R15") (pin "2") (pinfunction "2_2") (pintype "passive"))
      (node (ref "R25") (pin "2") (pinfunction "2_2") (pintype "passive"))
    )
    (net (code "22") (name "5VAUX") (class "Default")
      (node (ref "C21") (pin "2") (pinfunction "2_2") (pintype "passive"))
      (node (ref "C22") (pin "2") (pinfunction "2_2") (pintype "passive"))
      (node (ref "J1") (pin "9") (pinfunction "5VSB_9") (pintype "power_in"))
      (node (ref "P1") (pin "2") (pinfunction "2_2") (pintype "passive"))
      (node (ref "U7") (pin "10") (pinfunction "BIAS_10") (pintype "power_in"))
      (node (ref "U7") (pin "11") (pinfunction "EN_11") (pintype "input"))
      (node (ref "U7") (pin "5") (pinfunction "IN_5") (pintype "power_in"))
      (node (ref "U7") (pin "6") (pinfunction "IN_6") (pintype "power_in"))
      (node (ref "U7") (pin "7") (pinfunction "IN_7") (pintype "power_in"))
      (node (ref "U7") (pin "8") (pinfunction "IN_8") (pintype "power_in"))
    )
    (net (code "23") (name "5VMON") (class "Default")
      (node (ref "J1") (pin "21") (pinfunction "5V_21") (pintype "power_in"))
      (node (ref "J1") (pin "22") (pinfunction "5V_22") (pintype "power_in"))
      (node (ref "J1") (pin "23") (pinfunction "5V_23") (pintype "power_in"))
      (node (ref "J1") (pin "4") (pinfunction "5V_4") (pintype "power_in"))
      (node (ref "J1") (pin "6") (pinfunction "5V_6") (pintype "power_in"))
      (node (ref "P1") (pin "6") (pinfunction "6_6") (pintype "passive"))
      (node (ref "R25") (pin "1") (pinfunction "1_1") (pintype "passive"))
    )
    (net (code "24") (name "12V") (class "Default")
      (node (ref "C30") (pin "1") (pinfunction "1_1") (pintype "passive"))
      (node (ref "L1") (pin "1") (pinfunction "1_1") (pintype "passive"))
      (node (ref "L2") (pin "1") (pinfunction "1_1") (pintype "passive"))
      (node (ref "L3") (pin "1") (pinfunction "1_1") (pintype "passive"))
      (node (ref "R16") (pin "2") (pinfunction "2_2") (pintype "passive"))
      (node (ref "R24") (pin "2") (pinfunction "2_2") (pintype "passive"))
    )
    (net (code "25") (name "12VMON") (class "Default")
      (node (ref "J1") (pin "10") (pinfunction "12V_10") (pintype "power_in"))
      (node (ref "J1") (pin "11") (pinfunction "12V_11") (pintype "power_in"))
      (node (ref "P1") (pin "8") (pinfunction "8_8") (pintype "passive"))
      (node (ref "R24") (pin "1") (pinfunction "1_1") (pintype "passive"))
    )
    (net (code "26") (name "GND") (class "Default")
      (node (ref "C1") (pin "2") (pinfunction "2_2") (pintype "passive"))
      (node (ref "C10") (pin "1") (pinfunction "1_1") (pintype "passive"))
      (node (ref "C11") (pin "1") (pinfunction "1_1") (pintype "passive"))
      (node (ref "C12") (pin "1") (pinfunction "1_1") (pintype "passive"))
      (node (ref "C13") (pin "1") (pinfunction "1_1") (pintype "passive"))
      (node (ref "C14") (pin "1") (pinfunction "1_1") (pintype "passive"))
      (node (ref "C15") (pin "1") (pinfunction "1_1") (pintype "passive"))
      (node (ref "C16") (pin "1") (pinfunction "1_1") (pintype "passive"))
      (node (ref "C17") (pin "2") (pinfunction "2_2") (pintype "passive"))
      (node (ref "C18") (pin "1") (pinfunction "1_1") (pintype "passive"))
      (node (ref "C19") (pin "2") (pinfunction "2_2") (pintype "passive"))
      (node (ref "C2") (pin "1") (pinfunction "1_1") (pintype "passive"))
      (node (ref "C20") (pin "1") (pinfunction "1_1") (pintype "passive"))
      (node (ref "C21") (pin "1") (pinfunction "1_1") (pintype "passive"))
      (node (ref "C22") (pin "1") (pinfunction "1_1") (pintype "passive"))
      (node (ref "C23") (pin "2") (pinfunction "2_2") (pintype "passive"))
      (node (ref "C24") (pin "1") (pinfunction "1_1") (pintype "passive"))
      (node (ref "C25") (pin "1") (pinfunction "1_1") (pintype "passive"))
      (node (ref "C26") (pin "2") (pinfunction "2_2") (pintype "passive"))
      (node (ref "C27") (pin "1") (pinfunction "1_1") (pintype "passive"))
      (node (ref "C28") (pin "2") (pinfunction "2_2") (pintype "passive"))
      (node (ref "C29") (pin "1") (pinfunction "1_1") (pintype "passive"))
      (node (ref "C3") (pin "2") (pinfunction "2_2") (pintype "passive"))
      (node (ref "C30") (pin "2") (pinfunction "2_2") (pintype "passive"))
      (node (ref "C31") (pin "2") (pinfunction "2_2") (pintype "passive"))
      (node (ref "C32") (pin "2") (pinfunction "2_2") (pintype "passive"))
      (node (ref "C33") (pin "1") (pinfunction "1_1") (pintype "passive"))
      (node (ref "C34") (pin "2") (pinfunction "2_2") (pintype "passive"))
      (node (ref "C35") (pin "1") (pinfunction "1_1") (pintype "passive"))
      (node (ref "C36") (pin "2") (pinfunction "2_2") (pintype "passive"))
      (node (ref "C4") (pin "1") (pinfunction "1_1") (pintype "passive"))
      (node (ref "C5") (pin "2") (pinfunction "2_2") (pintype "passive"))
      (node (ref "C6") (pin "2") (pinfunction "2_2") (pintype "passive"))
      (node (ref "C7") (pin "1") (pinfunction "1_1") (pintype "passive"))
      (node (ref "C8") (pin "1") (pinfunction "1_1") (pintype "passive"))
      (node (ref "C9") (pin "1") (pinfunction "1_1") (pintype "passive"))
      (node (ref "J1") (pin "15") (pinfunction "COM_15") (pintype "power_in"))
      (node (ref "J1") (pin "17") (pinfunction "COM_17") (pintype "power_in"))
      (node (ref "J1") (pin "18") (pinfunction "COM_18") (pintype "power_in"))
      (node (ref "J1") (pin "19") (pinfunction "COM_19") (pintype "power_in"))
      (node (ref "J1") (pin "24") (pinfunction "COM_24") (pintype "power_in"))
      (node (ref "J1") (pin "3") (pinfunction "COM_3") (pintype "power_in"))
      (node (ref "J1") (pin "5") (pinfunction "COM_5") (pintype "power_in"))
      (node (ref "J1") (pin "7") (pinfunction "COM_7") (pintype "power_in"))
      (node (ref "JP1") (pin "2") (pinfunction "2_2") (pintype "passive"))
      (node (ref "P1") (pin "1") (pinfunction "1_1") (pintype "passive"))
      (node (ref "P1") (pin "3") (pinfunction "3_3") (pintype "passive"))
      (node (ref "P1") (pin "5") (pinfunction "5_5") (pintype "passive"))
      (node (ref "P1") (pin "7") (pinfunction "7_7") (pintype "passive"))
      (node (ref "P1") (pin "9") (pinfunction "9_9") (pintype "passive"))
      (node (ref "Q1") (pin "2") (pinfunction "S_2") (pintype "passive"))
      (node (ref "Q2") (pin "2") (pinfunction "S_2") (pintype "passive"))
      (node (ref "Q3") (pin "2") (pinfunction "S_2") (pintype "passive"))
      (node (ref "R14") (pin "1") (pinfunction "1_1") (pintype "passive"))
      (node (ref "R19") (pin "1") (pinfunction "1_1") (pintype "passive"))
      (node (ref "R22") (pin "1") (pinfunction "1_1") (pintype "passive"))
      (node (ref "R23") (pin "1") (pinfunction "1_1") (pintype "passive"))
      (node (ref "R30") (pin "1") (pinfunction "1_1") (pintype "passive"))
      (node (ref "R5") (pin "1") (pinfunction "1_1") (pintype "passive"))
      (node (ref "R8") (pin "1") (pinfunction "1_1") (pintype "passive"))
      (node (ref "R9") (pin "1") (pinfunction "1_1") (pintype "passive"))
      (node (ref "U10") (pin "2") (pinfunction "GND_2") (pintype "passive"))
      (node (ref "U3") (pin "1") (pinfunction "SMARTSYNC_1") (pintype "input"))
      (node (ref "U3") (pin "3") (pinfunction "GND_3") (pintype "power_in"))
      (node (ref "U3") (pin "4") (pinfunction "GND_4") (pintype "power_in"))
      (node (ref "U3") (pin "7") (pinfunction "SENSE_N_7") (pintype "input"))
      (node (ref "U4") (pin "12") (pinfunction "GND_12") (pintype "power_in"))
      (node (ref "U4") (pin "21") (pinfunction "TH_GND_21") (pintype "power_in"))
      (node (ref "U5") (pin "12") (pinfunction "GND_12") (pintype "power_in"))
      (node (ref "U5") (pin "21") (pinfunction "TH_GND_21") (pintype "power_in"))
      (node (ref "U6") (pin "1") (pinfunction "SMARTSYNC_1") (pintype "input"))
      (node (ref "U6") (pin "3") (pinfunction "GND_3") (pintype "power_in"))
      (node (ref "U6") (pin "4") (pinfunction "GND_4") (pintype "power_in"))
      (node (ref "U6") (pin "7") (pinfunction "SENSE_N_7") (pintype "input"))
      (node (ref "U7") (pin "12") (pinfunction "GND_12") (pintype "power_in"))
      (node (ref "U7") (pin "21") (pinfunction "TH_GND_21") (pintype "power_in"))
      (node (ref "U8") (pin "11") (pinfunction "SENSE_N_11") (pintype "power_in"))
      (node (ref "U8") (pin "3") (pinfunction "GND_3") (pintype "power_in"))
      (node (ref "U8") (pin "4") (pinfunction "GND_4") (pintype "power_in"))
      (node (ref "U8") (pin "7") (pinfunction "GND_7") (pintype "power_in"))
      (node (ref "U8") (pin "8") (pinfunction "GND_8") (pintype "power_in"))
      (node (ref "U9") (pin "1") (pinfunction "CONFIG_1") (pintype "input"))
      (node (ref "U9") (pin "12") (pinfunction "GND_12") (pintype "power_in"))
      (node (ref "U9") (pin "13") (pinfunction "GND_13") (pintype "power_in"))
      (node (ref "U9") (pin "16") (pinfunction "SENSE_N_16") (pintype "input"))
      (node (ref "U9") (pin "22") (pinfunction "SMARTSYNC_22") (pintype "input"))
      (node (ref "U9") (pin "8") (pinfunction "GND_8") (pintype "power_in"))
      (node (ref "U9") (pin "9") (pinfunction "GND_9") (pintype "power_in"))
      (node (ref "U90") (pin "2") (pinfunction "GND_2") (pintype "passive"))
      (node (ref "U91") (pin "2") (pinfunction "GND_2") (pintype "passive"))
    )
    (net (code "27") (name "MGT_1V0") (class "Default")
      (node (ref "C5") (pin "1") (pinfunction "1_1") (pintype "passive"))
      (node (ref "C9") (pin "2") (pinfunction "2_2") (pintype "passive"))
      (node (ref "R6") (pin "2") (pinfunction "2_2") (pintype "passive"))
      (node (ref "U4") (pin "1") (pinfunction "OUT_1") (pintype "power_in"))
      (node (ref "U4") (pin "18") (pinfunction "OUT_18") (pintype "power_in"))
      (node (ref "U4") (pin "19") (pinfunction "OUT_19") (pintype "power_in"))
      (node (ref "U4") (pin "20") (pinfunction "OUT_20") (pintype "power_in"))
    )
    (net (code "28") (name "MGT_1V2") (class "Default")
      (node (ref "C12") (pin "2") (pinfunction "2_2") (pintype "passive"))
      (node (ref "C6") (pin "1") (pinfunction "1_1") (pintype "passive"))
      (node (ref "R7") (pin "2") (pinfunction "2_2") (pintype "passive"))
      (node (ref "U5") (pin "1") (pinfunction "OUT_1") (pintype "power_in"))
      (node (ref "U5") (pin "18") (pinfunction "OUT_18") (pintype "power_in"))
      (node (ref "U5") (pin "19") (pinfunction "OUT_19") (pintype "power_in"))
      (node (ref "U5") (pin "20") (pinfunction "OUT_20") (pintype "power_in"))
    )
    (net (code "29") (name "N12V") (class "Default")
      (node (ref "J1") (pin "14") (pinfunction "-12V_14") (pintype "power_in"))
      (node (ref "P1") (pin "10") (pinfunction "10_10") (pintype "passive"))
    )
    (net (code "30") (name "Net-(C26-Pad1)") (class "Default")
      (node (ref "C26") (pin "1") (pinfunction "1_1") (pintype "passive"))
      (node (ref "C27") (pin "2") (pinfunction "2_2") (pintype "passive"))
      (node (ref "L3") (pin "2") (pinfunction "2_2") (pintype "passive"))
      (node (ref "U8") (pin "2") (pinfunction "VI_2") (pintype "power_in"))
      (node (ref "U8") (pin "6") (pinfunction "VI_6") (pintype "power_in"))
    )
    (net (code "31") (name "Net-(C32-Pad1)") (class "Default")
      (node (ref "C32") (pin "1") (pinfunction "1_1") (pintype "passive"))
      (node (ref "C33") (pin "2") (pinfunction "2_2") (pintype "passive"))
      (node (ref "L4") (pin "2") (pinfunction "2_2") (pintype "passive"))
      (node (ref "L5") (pin "2") (pinfunction "2_2") (pintype "passive"))
      (node (ref "L6") (pin "2") (pinfunction "2_2") (pintype "passive"))
      (node (ref "L7") (pin "2") (pinfunction "2_2") (pintype "passive"))
      (node (ref "U9") (pin "14") (pinfunction "VI_14") (pintype "power_in"))
      (node (ref "U9") (pin "15") (pinfunction "VI_15") (pintype "power_in"))
      (node (ref "U9") (pin "6") (pinfunction "VI_6") (pintype "power_in"))
      (node (ref "U9") (pin "7") (pinfunction "VI_7") (pintype "power_in"))
    )
    (net (code "32") (name "Net-(J1-PS_ONn)") (class "Default")
      (node (ref "J1") (pin "16") (pinfunction "PS_ONn_16") (pintype "input"))
      (node (ref "U90") (pin "4") (pinfunction "A_4") (pintype "passive"))
    )
    (net (code "33") (name "Net-(Q1-D)") (class "Default")
      (node (ref "Q1") (pin "3") (pinfunction "D_3") (pintype "passive"))
      (node (ref "R13") (pin "1") (pinfunction "1_1") (pintype "passive"))
    )
    (net (code "34") (name "Net-(Q1-G)") (class "Default")
      (node (ref "Q1") (pin "1") (pinfunction "G_1") (pintype "passive"))
      (node (ref "Q2") (pin "1") (pinfunction "G_1") (pintype "passive"))
      (node (ref "Q3") (pin "3") (pinfunction "D_3") (pintype "passive"))
      (node (ref "R15") (pin "1") (pinfunction "1_1") (pintype "passive"))
    )
    (net (code "35") (name "Net-(Q2-D)") (class "Default")
      (node (ref "Q2") (pin "3") (pinfunction "D_3") (pintype "passive"))
      (node (ref "R16") (pin "1") (pinfunction "1_1") (pintype "passive"))
    )
    (net (code "36") (name "Net-(Q3-G)") (class "Default")
      (node (ref "Q3") (pin "1") (pinfunction "G_1") (pintype "passive"))
      (node (ref "R20") (pin "1") (pinfunction "1_1") (pintype "passive"))
      (node (ref "R22") (pin "2") (pinfunction "2_2") (pintype "passive"))
    )
    (net (code "37") (name "Net-(U3-TRACK)") (class "Default")
      (node (ref "C1") (pin "1") (pinfunction "1_1") (pintype "passive"))
      (node (ref "C2") (pin "2") (pinfunction "2_2") (pintype "passive"))
      (node (ref "L1") (pin "2") (pinfunction "2_2") (pintype "passive"))
      (node (ref "U3") (pin "10") (pinfunction "TRACK_10") (pintype "input"))
      (node (ref "U3") (pin "2") (pinfunction "VI_2") (pintype "power_in"))
    )
    (net (code "38") (name "Net-(U3-TURBOTRANS)") (class "Default")
      (node (ref "R3") (pin "1") (pinfunction "1_1") (pintype "passive"))
      (node (ref "U3") (pin "9") (pinfunction "TURBOTRANS_9") (pintype "power_in"))
    )
    (net (code "39") (name "Net-(U3-VOADJ)") (class "Default")
      (node (ref "R5") (pin "2") (pinfunction "2_2") (pintype "passive"))
      (node (ref "U3") (pin "8") (pinfunction "VOADJ_8") (pintype "input"))
    )
    (net (code "40") (name "Net-(U4-FB)") (class "Default")
      (node (ref "R6") (pin "1") (pinfunction "1_1") (pintype "passive"))
      (node (ref "R8") (pin "2") (pinfunction "2_2") (pintype "passive"))
      (node (ref "U4") (pin "16") (pinfunction "FB_16") (pintype "input"))
    )
    (net (code "41") (name "Net-(U4-SS)") (class "Default")
      (node (ref "C13") (pin "2") (pinfunction "2_2") (pintype "passive"))
      (node (ref "U4") (pin "15") (pinfunction "SS_15") (pintype "passive"))
    )
    (net (code "42") (name "Net-(U5-FB)") (class "Default")
      (node (ref "R7") (pin "1") (pinfunction "1_1") (pintype "passive"))
      (node (ref "R9") (pin "2") (pinfunction "2_2") (pintype "passive"))
      (node (ref "U5") (pin "16") (pinfunction "FB_16") (pintype "input"))
    )
    (net (code "43") (name "Net-(U5-SS)") (class "Default")
      (node (ref "C14") (pin "2") (pinfunction "2_2") (pintype "passive"))
      (node (ref "U5") (pin "15") (pinfunction "SS_15") (pintype "passive"))
    )
    (net (code "44") (name "Net-(U6-TURBOTRANS)") (class "Default")
      (node (ref "R10") (pin "1") (pinfunction "1_1") (pintype "passive"))
      (node (ref "U6") (pin "9") (pinfunction "TURBOTRANS_9") (pintype "power_in"))
    )
    (net (code "45") (name "Net-(U6-VI)") (class "Default")
      (node (ref "C17") (pin "1") (pinfunction "1_1") (pintype "passive"))
      (node (ref "C18") (pin "2") (pinfunction "2_2") (pintype "passive"))
      (node (ref "L2") (pin "2") (pinfunction "2_2") (pintype "passive"))
      (node (ref "U6") (pin "2") (pinfunction "VI_2") (pintype "power_in"))
    )
    (net (code "46") (name "Net-(U6-VOADJ)") (class "Default")
      (node (ref "R14") (pin "2") (pinfunction "2_2") (pintype "passive"))
      (node (ref "U6") (pin "8") (pinfunction "VOADJ_8") (pintype "input"))
    )
    (net (code "47") (name "Net-(U7-FB)") (class "Default")
      (node (ref "R17") (pin "1") (pinfunction "1_1") (pintype "passive"))
      (node (ref "R19") (pin "2") (pinfunction "2_2") (pintype "passive"))
      (node (ref "U7") (pin "16") (pinfunction "FB_16") (pintype "input"))
    )
    (net (code "48") (name "Net-(U7-SS)") (class "Default")
      (node (ref "C25") (pin "2") (pinfunction "2_2") (pintype "passive"))
      (node (ref "U7") (pin "15") (pinfunction "SS_15") (pintype "passive"))
    )
    (net (code "49") (name "Net-(U8-TURBOTRANS)") (class "Default")
      (node (ref "R18") (pin "1") (pinfunction "1_1") (pintype "passive"))
      (node (ref "U8") (pin "13") (pinfunction "TURBOTRANS_13") (pintype "power_in"))
    )
    (net (code "50") (name "Net-(U8-VOADJ)") (class "Default")
      (node (ref "R23") (pin "2") (pinfunction "2_2") (pintype "passive"))
      (node (ref "U8") (pin "12") (pinfunction "VOADJ_12") (pintype "input"))
    )
    (net (code "51") (name "Net-(U9-AGND)") (class "Default")
      (node (ref "R29") (pin "1") (pinfunction "1_1") (pintype "passive"))
      (node (ref "U9") (pin "4") (pinfunction "AGND_4") (pintype "power_in"))
    )
    (net (code "52") (name "Net-(U9-TURBOTRANS)") (class "Default")
      (node (ref "R26") (pin "1") (pinfunction "1_1") (pintype "passive"))
      (node (ref "U9") (pin "19") (pinfunction "TURBOTRANS_19") (pintype "input"))
    )
    (net (code "53") (name "Net-(U9-VOADJ)") (class "Default")
      (node (ref "R29") (pin "2") (pinfunction "2_2") (pintype "passive"))
      (node (ref "U9") (pin "18") (pinfunction "VOADJ_18") (pintype "power_in"))
    )
    (net (code "54") (name "Net-(U10-A)") (class "Default")
      (node (ref "U10") (pin "4") (pinfunction "A_4") (pintype "passive"))
      (node (ref "U91") (pin "3") (pinfunction "B0_3") (pintype "passive"))
    )
    (net (code "55") (name "Net-(U10-B0)") (class "Default")
      (node (ref "JP1") (pin "1") (pinfunction "1_1") (pintype "passive"))
      (node (ref "R41") (pin "2") (pinfunction "2_2") (pintype "passive"))
      (node (ref "U10") (pin "3") (pinfunction "B0_3") (pintype "passive"))
      (node (ref "U10") (pin "6") (pinfunction "S_6") (pintype "passive"))
    )
    (net (code "56") (name "Net-(U90-B1)") (class "Default")
      (node (ref "U90") (pin "1") (pinfunction "B1_1") (pintype "passive"))
      (node (ref "U91") (pin "4") (pinfunction "A_4") (pintype "passive"))
    )
    (net (code "57") (name "unconnected-(J1-NC-Pad20)") (class "Default")
      (node (ref "J1") (pin "20") (pinfunction "NC_20") (pintype "power_in+no_connect"))
    )
    (net (code "58") (name "unconnected-(U3-INHIBIT{slash}UVLO-Pad11)") (class "Default")
      (node (ref "U3") (pin "11") (pinfunction "INHIBIT/UVLO_11") (pintype "input+no_connect"))
    )
    (net (code "59") (name "unconnected-(U4-NC-Pad2)") (class "Default")
      (node (ref "U4") (pin "2") (pinfunction "NC_2") (pintype "passive+no_connect"))
    )
    (net (code "60") (name "unconnected-(U4-NC-Pad3)") (class "Default")
      (node (ref "U4") (pin "3") (pinfunction "NC_3") (pintype "passive+no_connect"))
    )
    (net (code "61") (name "unconnected-(U4-NC-Pad4)") (class "Default")
      (node (ref "U4") (pin "4") (pinfunction "NC_4") (pintype "passive+no_connect"))
    )
    (net (code "62") (name "unconnected-(U4-NC-Pad13)") (class "Default")
      (node (ref "U4") (pin "13") (pinfunction "NC_13") (pintype "passive+no_connect"))
    )
    (net (code "63") (name "unconnected-(U4-NC-Pad14)") (class "Default")
      (node (ref "U4") (pin "14") (pinfunction "NC_14") (pintype "passive+no_connect"))
    )
    (net (code "64") (name "unconnected-(U4-NC-Pad17)") (class "Default")
      (node (ref "U4") (pin "17") (pinfunction "NC_17") (pintype "passive+no_connect"))
    )
    (net (code "65") (name "unconnected-(U5-NC-Pad2)") (class "Default")
      (node (ref "U5") (pin "2") (pinfunction "NC_2") (pintype "passive+no_connect"))
    )
    (net (code "66") (name "unconnected-(U5-NC-Pad3)") (class "Default")
      (node (ref "U5") (pin "3") (pinfunction "NC_3") (pintype "passive+no_connect"))
    )
    (net (code "67") (name "unconnected-(U5-NC-Pad4)") (class "Default")
      (node (ref "U5") (pin "4") (pinfunction "NC_4") (pintype "passive+no_connect"))
    )
    (net (code "68") (name "unconnected-(U5-NC-Pad13)") (class "Default")
      (node (ref "U5") (pin "13") (pinfunction "NC_13") (pintype "passive+no_connect"))
    )
    (net (code "69") (name "unconnected-(U5-NC-Pad14)") (class "Default")
      (node (ref "U5") (pin "14") (pinfunction "NC_14") (pintype "passive+no_connect"))
    )
    (net (code "70") (name "unconnected-(U5-NC-Pad17)") (class "Default")
      (node (ref "U5") (pin "17") (pinfunction "NC_17") (pintype "passive+no_connect"))
    )
    (net (code "71") (name "unconnected-(U6-INHIBIT{slash}UVLO-Pad11)") (class "Default")
      (node (ref "U6") (pin "11") (pinfunction "INHIBIT/UVLO_11") (pintype "input+no_connect"))
    )
    (net (code "72") (name "unconnected-(U7-NC-Pad2)") (class "Default")
      (node (ref "U7") (pin "2") (pinfunction "NC_2") (pintype "passive+no_connect"))
    )
    (net (code "73") (name "unconnected-(U7-NC-Pad3)") (class "Default")
      (node (ref "U7") (pin "3") (pinfunction "NC_3") (pintype "passive+no_connect"))
    )
    (net (code "74") (name "unconnected-(U7-NC-Pad4)") (class "Default")
      (node (ref "U7") (pin "4") (pinfunction "NC_4") (pintype "passive+no_connect"))
    )
    (net (code "75") (name "unconnected-(U7-NC-Pad13)") (class "Default")
      (node (ref "U7") (pin "13") (pinfunction "NC_13") (pintype "passive+no_connect"))
    )
    (net (code "76") (name "unconnected-(U7-NC-Pad14)") (class "Default")
      (node (ref "U7") (pin "14") (pinfunction "NC_14") (pintype "passive+no_connect"))
    )
    (net (code "77") (name "unconnected-(U7-NC-Pad17)") (class "Default")
      (node (ref "U7") (pin "17") (pinfunction "NC_17") (pintype "passive+no_connect"))
    )
    (net (code "78") (name "unconnected-(U8-INHIBIT{slash}UVLO-Pad1)") (class "Default")
      (node (ref "U8") (pin "1") (pinfunction "INHIBIT/UVLO_1") (pintype "input+no_connect"))
    )
    (net (code "79") (name "unconnected-(U9-CLKIO-Pad5)") (class "Default")
      (node (ref "U9") (pin "5") (pinfunction "CLKIO_5") (pintype "input+no_connect"))
    )
    (net (code "80") (name "unconnected-(U9-COMP-Pad3)") (class "Default")
      (node (ref "U9") (pin "3") (pinfunction "COMP_3") (pintype "input+no_connect"))
    )
    (net (code "81") (name "unconnected-(U9-INHIBIT{slash}UVLO-Pad21)") (class "Default")
      (node (ref "U9") (pin "21") (pinfunction "INHIBIT/UVLO_21") (pintype "input+no_connect"))
    )
    (net (code "82") (name "unconnected-(U9-SHARE-Pad2)") (class "Default")
      (node (ref "U9") (pin "2") (pinfunction "SHARE_2") (pintype "input+no_connect"))
    )
    (net (code "83") (name "unconnected-(U90-B0-Pad3)") (class "Default")
      (node (ref "U90") (pin "3") (pinfunction "B0_3") (pintype "passive+no_connect"))
    )
  )
)
